# 04_-_ETHERCAT.net
KiCad netlist of a schematic drawn in Altium Designer
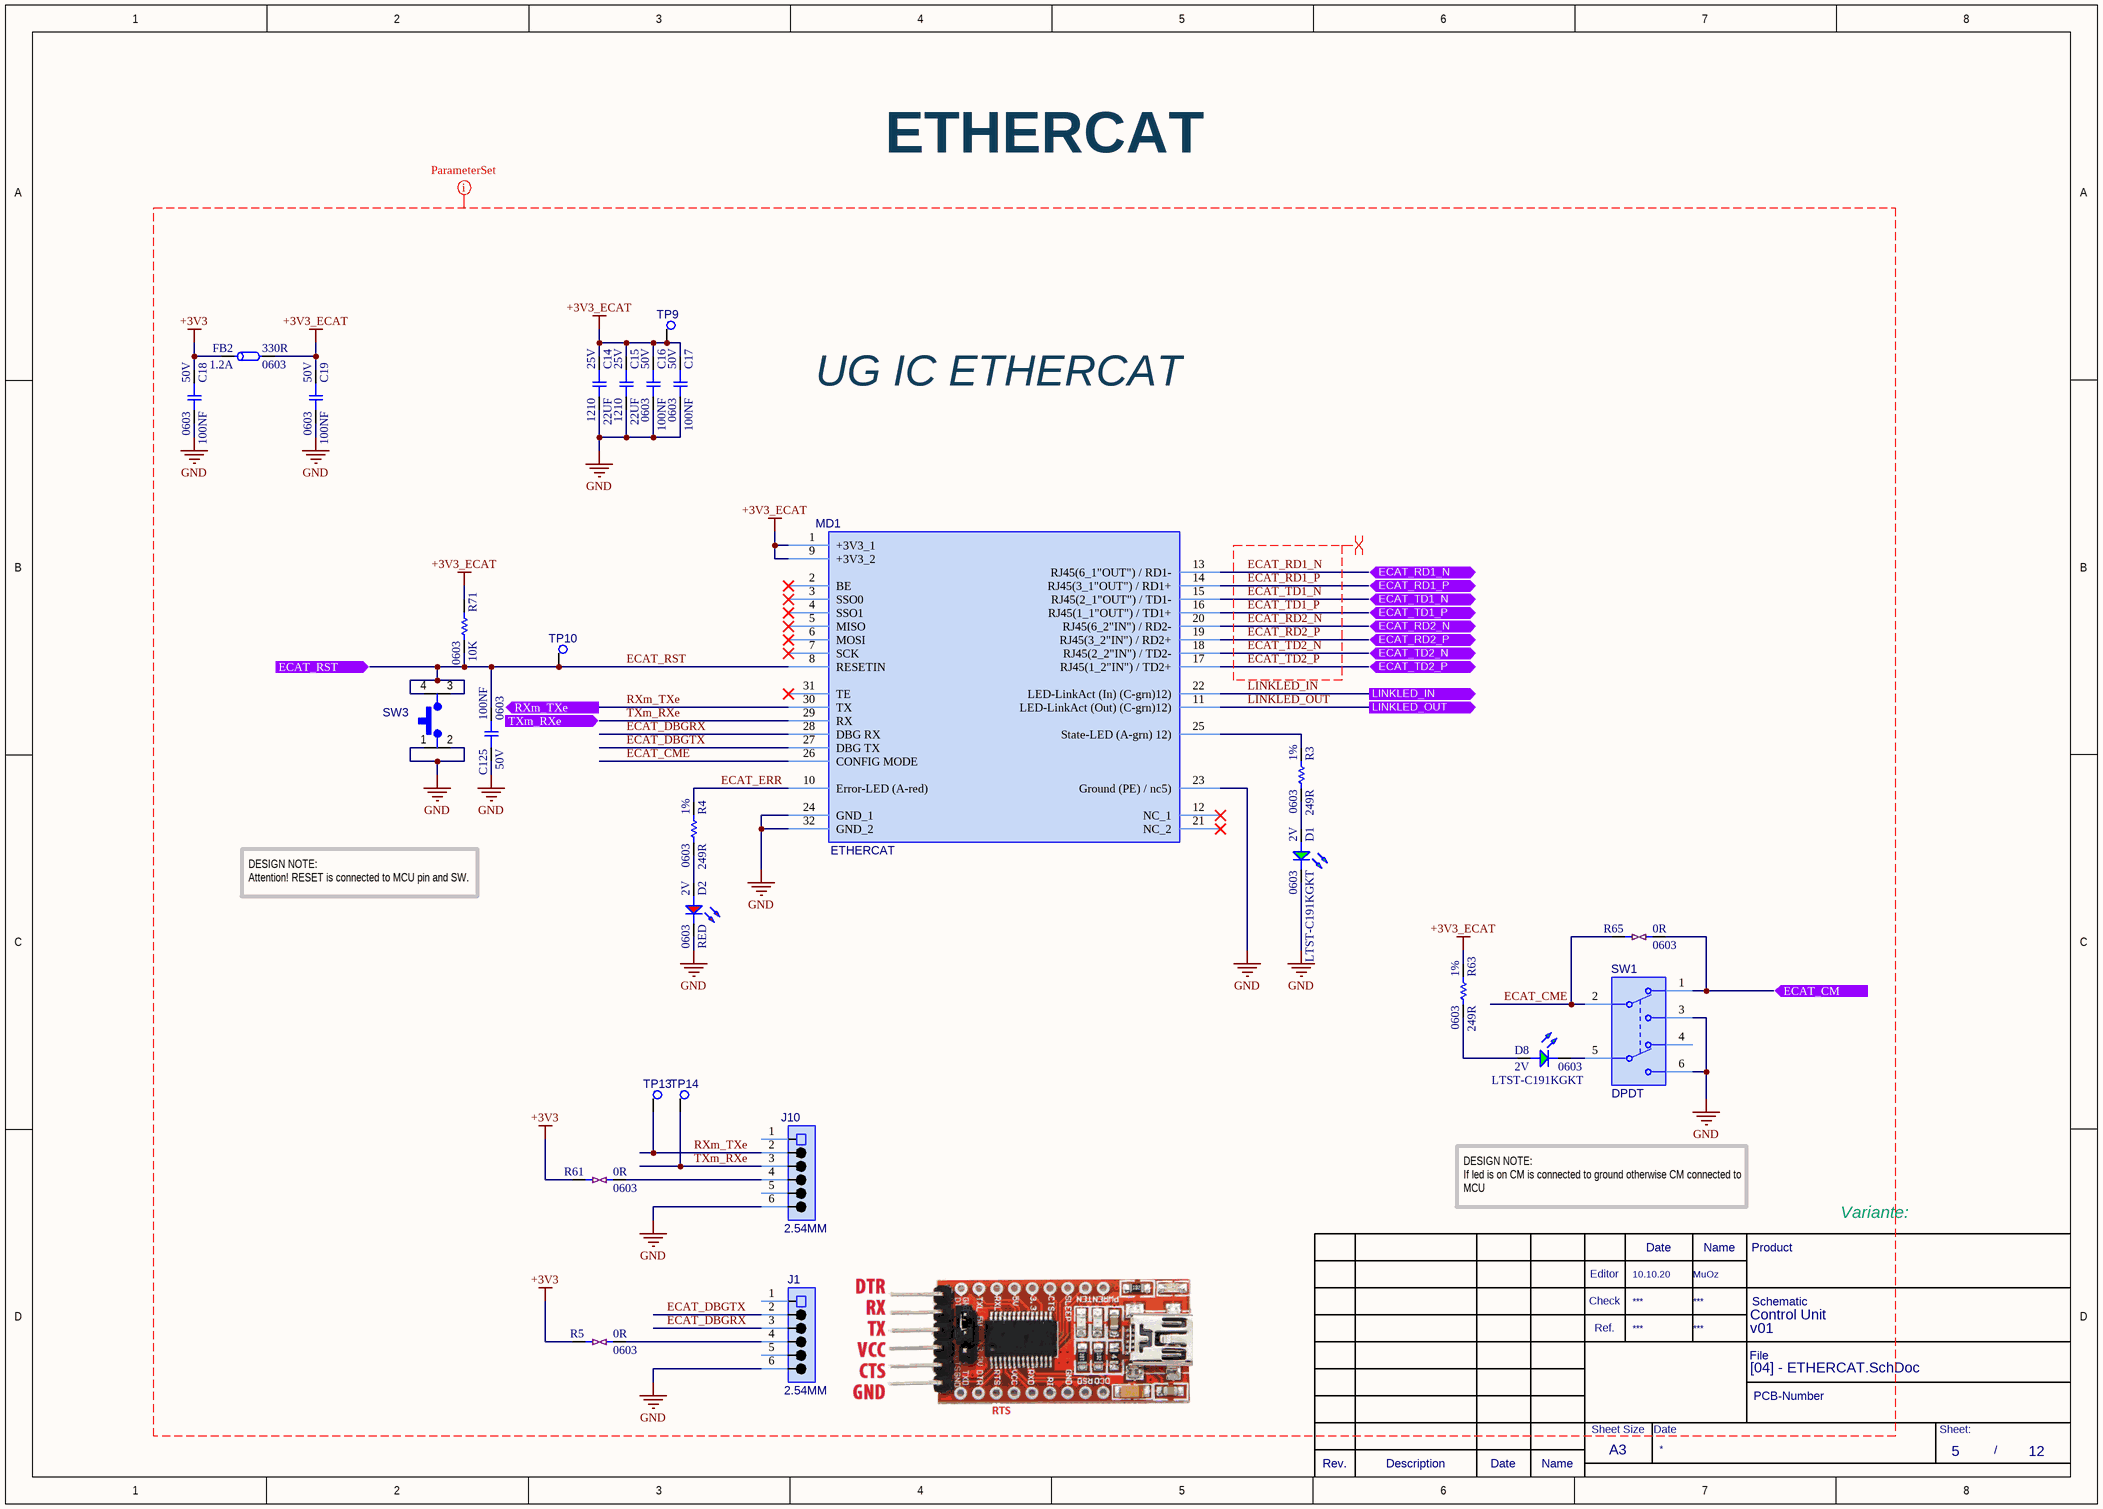
[diagram p0: [04] - ETHERCAT.SchDoc]

(export (version "E")
  (design (tool "Eeschema 10.0.6"))
  (components
    (comp (ref "C14")
      (value "22UF")
      (footprint "C-1210")
      (description "CAP CER 22UF 25V X7R 1210")
      (fields
        (field (name "MANUFACTURER") "Samsung")
        (field (name "MANUFACTURER PART NUMBER") "CL32B226KAJNNNE")
        (field (name "VOLTAGE RATING") "25V")
        (field (name "CASE CODE (IMPERIAL)") "1210")
        (field (name ".CREATOR") "F:TALI")
      )
      (libsource (lib "BARKO_SCHLIB") (part "C-22UF-1210"))
    )
    (comp (ref "C15")
      (value "22UF")
      (footprint "C-1210")
      (description "CAP CER 22UF 25V X7R 1210")
      (fields
        (field (name "MANUFACTURER") "Samsung")
        (field (name "MANUFACTURER PART NUMBER") "CL32B226KAJNNNE")
        (field (name "VOLTAGE RATING") "25V")
        (field (name "CASE CODE (IMPERIAL)") "1210")
        (field (name ".CREATOR") "F:TALI")
      )
      (libsource (lib "BARKO_SCHLIB") (part "C-22UF-1210"))
    )
    (comp (ref "C16")
      (value "100NF")
      (footprint "C-0603")
      (description "CAP CER 0.1UF 50V X7R 0603")
      (fields
        (field (name "MANUFACTURER") "TDK")
        (field (name "MANUFACTURER PART NUMBER") "C1608X7R1H104K080AA")
        (field (name "VOLTAGE RATING") "50V")
        (field (name "CASE CODE (IMPERIAL)") "0603")
        (field (name ".CREATOR") "F:TALI")
      )
      (libsource (lib "BARKO_SCHLIB") (part "C-100NF-0603"))
    )
    (comp (ref "C17")
      (value "100NF")
      (footprint "C-0603")
      (description "CAP CER 0.1UF 50V X7R 0603")
      (fields
        (field (name "MANUFACTURER") "TDK")
        (field (name "MANUFACTURER PART NUMBER") "C1608X7R1H104K080AA")
        (field (name "VOLTAGE RATING") "50V")
        (field (name "CASE CODE (IMPERIAL)") "0603")
        (field (name ".CREATOR") "F:TALI")
      )
      (libsource (lib "BARKO_SCHLIB") (part "C-100NF-0603"))
    )
    (comp (ref "C18")
      (value "100NF")
      (footprint "C-0603")
      (description "CAP CER 0.1UF 50V X7R 0603")
      (fields
        (field (name "MANUFACTURER") "TDK")
        (field (name "MANUFACTURER PART NUMBER") "C1608X7R1H104K080AA")
        (field (name "VOLTAGE RATING") "50V")
        (field (name "CASE CODE (IMPERIAL)") "0603")
        (field (name ".CREATOR") "F:TALI")
      )
      (libsource (lib "BARKO_SCHLIB") (part "C-100NF-0603"))
    )
    (comp (ref "C19")
      (value "100NF")
      (footprint "C-0603")
      (description "CAP CER 0.1UF 50V X7R 0603")
      (fields
        (field (name "MANUFACTURER") "TDK")
        (field (name "MANUFACTURER PART NUMBER") "C1608X7R1H104K080AA")
        (field (name "VOLTAGE RATING") "50V")
        (field (name "CASE CODE (IMPERIAL)") "0603")
        (field (name ".CREATOR") "F:TALI")
      )
      (libsource (lib "BARKO_SCHLIB") (part "C-100NF-0603"))
    )
    (comp (ref "C125")
      (value "100NF")
      (footprint "C-0603")
      (description "CAP CER 0.1UF 50V X7R 0603")
      (fields
        (field (name "MANUFACTURER") "TDK")
        (field (name "MANUFACTURER PART NUMBER") "C1608X7R1H104K080AA")
        (field (name "VOLTAGE RATING") "50V")
        (field (name "CASE CODE (IMPERIAL)") "0603")
        (field (name ".CREATOR") "F:TALI")
      )
      (libsource (lib "BARKO_SCHLIB") (part "C-100NF-0603"))
    )
    (comp (ref "D1")
      (value "LTST-C191KGKT")
      (footprint "LED-0603-GREEN")
      (description "LED GREEN CLEAR 0603 SMD")
      (fields
        (field (name "MANUFACTURER") "Vishay Lite-On")
        (field (name "FORWARD VOLTAGE") "2V")
        (field (name "CASE CODE (IMPERIAL)") "0603")
        (field (name ".CREATOR") "F:TALI")
      )
      (libsource (lib "BARKO_SCHLIB") (part "LED-GREEN-0603"))
    )
    (comp (ref "D2")
      (value "RED")
      (footprint "LED-0603")
      (description "LED RED CLEAR 0603 SMD")
      (fields
        (field (name "MANUFACTURER") "Wurth Electronics")
        (field (name "MANUFACTURER PART NUMBER") "150060RS75000")
        (field (name "CASE/PACKAGE") "0603")
        (field (name "FORWARD VOLTAGE") "2V")
      )
      (libsource (lib "BARKO_SCHLIB") (part "LED-RED-0603"))
    )
    (comp (ref "D8")
      (value "LTST-C191KGKT")
      (footprint "LED-0603-GREEN")
      (description "LED GREEN CLEAR 0603 SMD")
      (fields
        (field (name "MANUFACTURER") "Vishay Lite-On")
        (field (name "FORWARD VOLTAGE") "2V")
        (field (name "CASE CODE (IMPERIAL)") "0603")
        (field (name ".CREATOR") "F:TALI")
      )
      (libsource (lib "BARKO_SCHLIB") (part "LED-GREEN-0603"))
    )
    (comp (ref "FB2")
      (value "330R")
      (footprint "FB-0603")
      (description "FERRITE BEAD 330 OHM 0603 1LN")
      (fields
        (field (name "MANUFACTURER") "Murata")
        (field (name "MANUFACTURER PART NUMBER") "BLM18PG331SN1D")
        (field (name "CASE/PACKAGE") "0603")
        (field (name "DC CURRENT") "1.2A")
        (field (name ".CREATOR") "M.OZKAN")
      )
      (libsource (lib "BARKO_SCHLIB") (part "FB-330R-0603"))
    )
    (comp (ref "J1")
      (value "2.54MM")
      (footprint "CON-1X6-VERT-2.54MM")
      (description "CONN RCPT 6POS 0.1 TIN PCB")
      (fields (field (name "MANUFACTURER PART NUMBER") "M20-7820646"))
      (libsource (lib "SCHLIB") (part "CON-6POS-2.54MM"))
    )
    (comp (ref "J10")
      (value "2.54MM")
      (footprint "CON-1X6-VERT-2.54MM")
      (description "CONN RCPT 6POS 0.1 TIN PCB")
      (fields (field (name "MANUFACTURER PART NUMBER") "M20-7820646"))
      (libsource (lib "SCHLIB") (part "CON-6POS-2.54MM"))
    )
    (comp (ref "MD1")
      (value "ETHERCAT")
      (footprint "MD-UG-IC-PIN")
      (description "UNIGATE® IC - EtherCAT®")
      (libsource (lib "SCHLIB") (part "MD-UG IC ETHERCAT"))
    )
    (comp (ref "R3")
      (value "249R")
      (footprint "R-0603")
      (description "RES 249 OHM 1% 1/10W 0603")
      (fields
        (field (name "MANUFACTURER") "Stackpole Electronics")
        (field (name "MANUFACTURER PART NUMBER") "RMCF0603FT249R")
        (field (name "TOLERANCE") "1%")
        (field (name "CASE/PACKAGE") "0603")
      )
      (libsource (lib "BARKO_SCHLIB") (part "R-249R-0603"))
    )
    (comp (ref "R4")
      (value "249R")
      (footprint "R-0603")
      (description "RES 249 OHM 1% 1/10W 0603")
      (fields
        (field (name "MANUFACTURER") "Stackpole Electronics")
        (field (name "MANUFACTURER PART NUMBER") "RMCF0603FT249R")
        (field (name "TOLERANCE") "1%")
        (field (name "CASE/PACKAGE") "0603")
      )
      (libsource (lib "BARKO_SCHLIB") (part "R-249R-0603"))
    )
    (comp (ref "R5")
      (value "0R")
      (footprint "JMP-0603")
      (description "RES SMD 0 OHM 1/10W JUMP 0603")
      (fields
        (field (name "MANUFACTURER") "Yageo")
        (field (name "MANUFACTURER PART NUMBER") "RC0603JR-070RL")
        (field (name "CASE CODE (IMPERIAL)") "0603")
        (field (name ".CREATOR") "F:TALI")
      )
      (libsource (lib "BARKO_SCHLIB") (part "R-0R-0603"))
    )
    (comp (ref "R61")
      (value "0R")
      (footprint "JMP-0603")
      (description "RES SMD 0 OHM 1/10W JUMP 0603")
      (fields
        (field (name "MANUFACTURER") "Yageo")
        (field (name "MANUFACTURER PART NUMBER") "RC0603JR-070RL")
        (field (name "CASE CODE (IMPERIAL)") "0603")
        (field (name ".CREATOR") "F:TALI")
      )
      (libsource (lib "BARKO_SCHLIB") (part "R-0R-0603"))
    )
    (comp (ref "R63")
      (value "249R")
      (footprint "R-0603")
      (description "RES 249 OHM 1% 1/10W 0603")
      (fields
        (field (name "MANUFACTURER") "Stackpole Electronics")
        (field (name "MANUFACTURER PART NUMBER") "RMCF0603FT249R")
        (field (name "TOLERANCE") "1%")
        (field (name "CASE/PACKAGE") "0603")
      )
      (libsource (lib "BARKO_SCHLIB") (part "R-249R-0603"))
    )
    (comp (ref "R65")
      (value "0R")
      (footprint "JMP-0603")
      (description "RES SMD 0 OHM 1/10W JUMP 0603")
      (fields
        (field (name "MANUFACTURER") "Yageo")
        (field (name "MANUFACTURER PART NUMBER") "RC0603JR-070RL")
        (field (name "CASE CODE (IMPERIAL)") "0603")
        (field (name ".CREATOR") "F:TALI")
      )
      (libsource (lib "BARKO_SCHLIB") (part "R-0R-0603"))
    )
    (comp (ref "R71")
      (value "10K")
      (footprint "R-0603")
      (description "RES SMD 10K OHM 1% 1/10W 0603")
      (fields
        (field (name "MANUFACTURER") "Yageo")
        (field (name "MANUFACTURER PART NUMBER") "RC0603FR-0710KL")
        (field (name "CASE CODE (IMPERIAL)") "0603")
        (field (name ".CREATOR") "F:TALI")
      )
      (libsource (lib "BARKO_SCHLIB") (part "R-10K-0603"))
    )
    (comp (ref "SW1")
      (value "DPDT")
      (footprint "SW-AYZ0202AGRLC")
      (description "SWITCH SLIDE DPDT 100MA 12V")
      (fields
        (field (name "MANUFACTURER") "ITT C&K")
        (field (name "MANUFACTURER PART NUMBER") "AYZ0202AGRLC")
      )
      (libsource (lib "SCHLIB") (part "SW-AYZ0202AGRLC"))
    )
    (comp (ref "SW3")
      (value "SW-TACTILE-5MM")
      (footprint "TACTILE_SMD_V2")
      (description "SWITCH TACTILE SPST-NO 0.05A 24V")
      (fields
        (field (name "MANUFACTURER") "TE Connectivity AMP")
        (field (name "MANUFACTURER PART NUMBER") "FSM4JSMA")
        (field (name ".CREATOR") "F:TALI")
      )
      (libsource (lib "BARKO_SCHLIB") (part "SW-TACTILE-5MM"))
    )
    (comp (ref "TP9")
      (value "MECH-TESTPOINT")
      (footprint "MECH-TESTPOINT")
      (fields (field (name ".CREATOR") "F:TALI"))
      (libsource (lib "BARKO_SCHLIB") (part "MECH-TESTPOINT"))
    )
    (comp (ref "TP10")
      (value "MECH-TESTPOINT")
      (footprint "MECH-TESTPOINT")
      (fields (field (name ".CREATOR") "F:TALI"))
      (libsource (lib "BARKO_SCHLIB") (part "MECH-TESTPOINT"))
    )
    (comp (ref "TP13")
      (value "MECH-TESTPOINT")
      (footprint "MECH-TESTPOINT")
      (fields (field (name ".CREATOR") "F:TALI"))
      (libsource (lib "BARKO_SCHLIB") (part "MECH-TESTPOINT"))
    )
    (comp (ref "TP14")
      (value "MECH-TESTPOINT")
      (footprint "MECH-TESTPOINT")
      (fields (field (name ".CREATOR") "F:TALI"))
      (libsource (lib "BARKO_SCHLIB") (part "MECH-TESTPOINT"))
    )
  )
  (nets
    (net (code "1") (name "+3V3") (class "Default")
      (node (ref "C18") (pin "1") (pinfunction "1_1") (pintype "passive"))
      (node (ref "FB2") (pin "1") (pinfunction "1_1") (pintype "passive"))
      (node (ref "R5") (pin "1") (pinfunction "1_1") (pintype "passive"))
      (node (ref "R61") (pin "1") (pinfunction "1_1") (pintype "passive"))
    )
    (net (code "2") (name "+3V3_ECAT") (class "Default")
      (node (ref "C14") (pin "1") (pinfunction "1_1") (pintype "passive"))
      (node (ref "C15") (pin "1") (pinfunction "1_1") (pintype "passive"))
      (node (ref "C16") (pin "1") (pinfunction "1_1") (pintype "passive"))
      (node (ref "C17") (pin "1") (pinfunction "1_1") (pintype "passive"))
      (node (ref "C19") (pin "1") (pinfunction "1_1") (pintype "passive"))
      (node (ref "FB2") (pin "2") (pinfunction "2_2") (pintype "passive"))
      (node (ref "MD1") (pin "1") (pinfunction "+3V3_1_1") (pintype "passive"))
      (node (ref "MD1") (pin "9") (pinfunction "+3V3_2_9") (pintype "passive"))
      (node (ref "R63") (pin "1") (pinfunction "1_1") (pintype "passive"))
      (node (ref "R71") (pin "1") (pinfunction "1_1") (pintype "passive"))
      (node (ref "TP9") (pin "1") (pinfunction "1_1") (pintype "passive"))
    )
    (net (code "3") (name "/ECAT_CM") (class "Default")
      (node (ref "R65") (pin "2") (pinfunction "2_2") (pintype "passive"))
      (node (ref "SW1") (pin "1") (pinfunction "1_1") (pintype "passive"))
    )
    (net (code "4") (name "/ECAT_CME") (class "Default")
      (node (ref "MD1") (pin "26") (pinfunction "CONFIG_MODE_26") (pintype "passive"))
      (node (ref "R65") (pin "1") (pinfunction "1_1") (pintype "passive"))
      (node (ref "SW1") (pin "2") (pinfunction "2_2") (pintype "passive"))
    )
    (net (code "5") (name "/ECAT_DBGRX") (class "Default")
      (node (ref "J1") (pin "3") (pinfunction "3_3") (pintype "passive"))
      (node (ref "MD1") (pin "28") (pinfunction "DBG_RX_28") (pintype "passive"))
    )
    (net (code "6") (name "/ECAT_DBGTX") (class "Default")
      (node (ref "J1") (pin "2") (pinfunction "2_2") (pintype "passive"))
      (node (ref "MD1") (pin "27") (pinfunction "DBG_TX_27") (pintype "passive"))
    )
    (net (code "7") (name "/ECAT_ERR") (class "Default")
      (node (ref "MD1") (pin "10") (pinfunction "Error-LED_(A-red)_10") (pintype "passive"))
      (node (ref "R4") (pin "1") (pinfunction "1_1") (pintype "passive"))
    )
    (net (code "8") (name "/ECAT_RD1_N") (class "Default")
      (node (ref "MD1") (pin "13") (pinfunction "RJ45(6_1\"OUT\")_/_RD1-_13") (pintype "passive"))
    )
    (net (code "9") (name "/ECAT_RD1_P") (class "Default")
      (node (ref "MD1") (pin "14") (pinfunction "RJ45(3_1\"OUT\")_/_RD1+_14") (pintype "passive"))
    )
    (net (code "10") (name "/ECAT_RD2_N") (class "Default")
      (node (ref "MD1") (pin "20") (pinfunction "RJ45(6_2\"IN\")_/_RD2-_20") (pintype "passive"))
    )
    (net (code "11") (name "/ECAT_RD2_P") (class "Default")
      (node (ref "MD1") (pin "19") (pinfunction "RJ45(3_2\"IN\")_/_RD2+_19") (pintype "passive"))
    )
    (net (code "12") (name "/ECAT_RST") (class "Default")
      (node (ref "C125") (pin "2") (pinfunction "2_2") (pintype "passive"))
      (node (ref "MD1") (pin "8") (pinfunction "RESETIN_8") (pintype "passive"))
      (node (ref "R71") (pin "2") (pinfunction "2_2") (pintype "passive"))
      (node (ref "SW3") (pin "3") (pinfunction "3_3") (pintype "passive"))
      (node (ref "SW3") (pin "4") (pinfunction "4_4") (pintype "passive"))
      (node (ref "TP10") (pin "1") (pinfunction "1_1") (pintype "passive"))
    )
    (net (code "13") (name "/ECAT_TD1_N") (class "Default")
      (node (ref "MD1") (pin "15") (pinfunction "RJ45(2_1\"OUT\")_/_TD1-_15") (pintype "passive"))
    )
    (net (code "14") (name "/ECAT_TD1_P") (class "Default")
      (node (ref "MD1") (pin "16") (pinfunction "RJ45(1_1\"OUT\")_/_TD1+_16") (pintype "passive"))
    )
    (net (code "15") (name "/ECAT_TD2_N") (class "Default")
      (node (ref "MD1") (pin "18") (pinfunction "RJ45(2_2\"IN\")_/_TD2-_18") (pintype "passive"))
    )
    (net (code "16") (name "/ECAT_TD2_P") (class "Default")
      (node (ref "MD1") (pin "17") (pinfunction "RJ45(1_2\"IN\")_/_TD2+_17") (pintype "passive"))
    )
    (net (code "17") (name "/LINKLED_IN") (class "Default")
      (node (ref "MD1") (pin "22") (pinfunction "LED-LinkAct_(In)_(C-grn)12)_22") (pintype "passive"))
    )
    (net (code "18") (name "/LINKLED_OUT") (class "Default")
      (node (ref "MD1") (pin "11") (pinfunction "LED-LinkAct_(Out)_(C-grn)12)_11") (pintype "passive"))
    )
    (net (code "19") (name "/RXm_TXe") (class "Default")
      (node (ref "J10") (pin "2") (pinfunction "2_2") (pintype "passive"))
      (node (ref "MD1") (pin "30") (pinfunction "TX_30") (pintype "passive"))
      (node (ref "TP13") (pin "1") (pinfunction "1_1") (pintype "passive"))
    )
    (net (code "20") (name "/TXm_RXe") (class "Default")
      (node (ref "J10") (pin "3") (pinfunction "3_3") (pintype "passive"))
      (node (ref "MD1") (pin "29") (pinfunction "RX_29") (pintype "passive"))
      (node (ref "TP14") (pin "1") (pinfunction "1_1") (pintype "passive"))
    )
    (net (code "21") (name "GND") (class "Default")
      (node (ref "C125") (pin "1") (pinfunction "1_1") (pintype "passive"))
      (node (ref "C14") (pin "2") (pinfunction "2_2") (pintype "passive"))
      (node (ref "C15") (pin "2") (pinfunction "2_2") (pintype "passive"))
      (node (ref "C16") (pin "2") (pinfunction "2_2") (pintype "passive"))
      (node (ref "C17") (pin "2") (pinfunction "2_2") (pintype "passive"))
      (node (ref "C18") (pin "2") (pinfunction "2_2") (pintype "passive"))
      (node (ref "C19") (pin "2") (pinfunction "2_2") (pintype "passive"))
      (node (ref "D1") (pin "C") (pinfunction "C_C") (pintype "passive"))
      (node (ref "D2") (pin "C") (pinfunction "C_C") (pintype "passive"))
      (node (ref "J1") (pin "6") (pinfunction "6_6") (pintype "passive"))
      (node (ref "J10") (pin "6") (pinfunction "6_6") (pintype "passive"))
      (node (ref "MD1") (pin "23") (pinfunction "Ground_(PE)_/_nc5)_23") (pintype "passive"))
      (node (ref "MD1") (pin "24") (pinfunction "GND_1_24") (pintype "passive"))
      (node (ref "MD1") (pin "32") (pinfunction "GND_2_32") (pintype "passive"))
      (node (ref "SW1") (pin "3") (pinfunction "3_3") (pintype "passive"))
      (node (ref "SW1") (pin "6") (pinfunction "6_6") (pintype "passive"))
      (node (ref "SW3") (pin "1") (pinfunction "1_1") (pintype "passive"))
      (node (ref "SW3") (pin "2") (pinfunction "2_2") (pintype "passive"))
    )
    (net (code "22") (name "Net-(D1-PadA)") (class "Default")
      (node (ref "D1") (pin "A") (pinfunction "A_A") (pintype "passive"))
      (node (ref "R3") (pin "2") (pinfunction "2_2") (pintype "passive"))
    )
    (net (code "23") (name "Net-(D2-PadA)") (class "Default")
      (node (ref "D2") (pin "A") (pinfunction "A_A") (pintype "passive"))
      (node (ref "R4") (pin "2") (pinfunction "2_2") (pintype "passive"))
    )
    (net (code "24") (name "Net-(D8-PadA)") (class "Default")
      (node (ref "D8") (pin "A") (pinfunction "A_A") (pintype "passive"))
      (node (ref "R63") (pin "2") (pinfunction "2_2") (pintype "passive"))
    )
    (net (code "25") (name "Net-(D8-PadC)") (class "Default")
      (node (ref "D8") (pin "C") (pinfunction "C_C") (pintype "passive"))
      (node (ref "SW1") (pin "5") (pinfunction "5_5") (pintype "passive"))
    )
    (net (code "26") (name "Net-(J1-Pad4)") (class "Default")
      (node (ref "J1") (pin "4") (pinfunction "4_4") (pintype "passive"))
      (node (ref "R5") (pin "2") (pinfunction "2_2") (pintype "passive"))
    )
    (net (code "27") (name "Net-(J10-Pad4)") (class "Default")
      (node (ref "J10") (pin "4") (pinfunction "4_4") (pintype "passive"))
      (node (ref "R61") (pin "2") (pinfunction "2_2") (pintype "passive"))
    )
    (net (code "28") (name "Net-(MD1-State-LED_(A-grn)_12))") (class "Default")
      (node (ref "MD1") (pin "25") (pinfunction "State-LED_(A-grn)_12)_25") (pintype "passive"))
      (node (ref "R3") (pin "1") (pinfunction "1_1") (pintype "passive"))
    )
    (net (code "29") (name "unconnected-(J1-GND_IN-Pad1)") (class "Default")
      (node (ref "J1") (pin "1") (pinfunction "GND_IN_1") (pintype "passive"))
    )
    (net (code "30") (name "unconnected-(J1-Pad5)") (class "Default")
      (node (ref "J1") (pin "5") (pinfunction "5_5") (pintype "passive"))
    )
    (net (code "31") (name "unconnected-(J10-GND_IN-Pad1)") (class "Default")
      (node (ref "J10") (pin "1") (pinfunction "GND_IN_1") (pintype "passive"))
    )
    (net (code "32") (name "unconnected-(J10-Pad5)") (class "Default")
      (node (ref "J10") (pin "5") (pinfunction "5_5") (pintype "passive"))
    )
    (net (code "33") (name "unconnected-(MD1-BE-Pad2)") (class "Default")
      (node (ref "MD1") (pin "2") (pinfunction "BE_2") (pintype "passive+no_connect"))
    )
    (net (code "34") (name "unconnected-(MD1-MISO-Pad5)") (class "Default")
      (node (ref "MD1") (pin "5") (pinfunction "MISO_5") (pintype "passive+no_connect"))
    )
    (net (code "35") (name "unconnected-(MD1-MOSI-Pad6)") (class "Default")
      (node (ref "MD1") (pin "6") (pinfunction "MOSI_6") (pintype "passive+no_connect"))
    )
    (net (code "36") (name "unconnected-(MD1-NC_1-Pad12)") (class "Default")
      (node (ref "MD1") (pin "12") (pinfunction "NC_1_12") (pintype "passive+no_connect"))
    )
    (net (code "37") (name "unconnected-(MD1-NC_2-Pad21)") (class "Default")
      (node (ref "MD1") (pin "21") (pinfunction "NC_2_21") (pintype "passive+no_connect"))
    )
    (net (code "38") (name "unconnected-(MD1-SCK-Pad7)") (class "Default")
      (node (ref "MD1") (pin "7") (pinfunction "SCK_7") (pintype "passive+no_connect"))
    )
    (net (code "39") (name "unconnected-(MD1-SSO0-Pad3)") (class "Default")
      (node (ref "MD1") (pin "3") (pinfunction "SSO0_3") (pintype "passive+no_connect"))
    )
    (net (code "40") (name "unconnected-(MD1-SSO1-Pad4)") (class "Default")
      (node (ref "MD1") (pin "4") (pinfunction "SSO1_4") (pintype "passive+no_connect"))
    )
    (net (code "41") (name "unconnected-(MD1-TE-Pad31)") (class "Default")
      (node (ref "MD1") (pin "31") (pinfunction "TE_31") (pintype "passive+no_connect"))
    )
    (net (code "42") (name "unconnected-(SW1-Pad4)") (class "Default")
      (node (ref "SW1") (pin "4") (pinfunction "4_4") (pintype "passive"))
    )
  )
)
